# Distribution_amp_10Mhz.net
KiCad netlist of a schematic drawn in Altium Designer
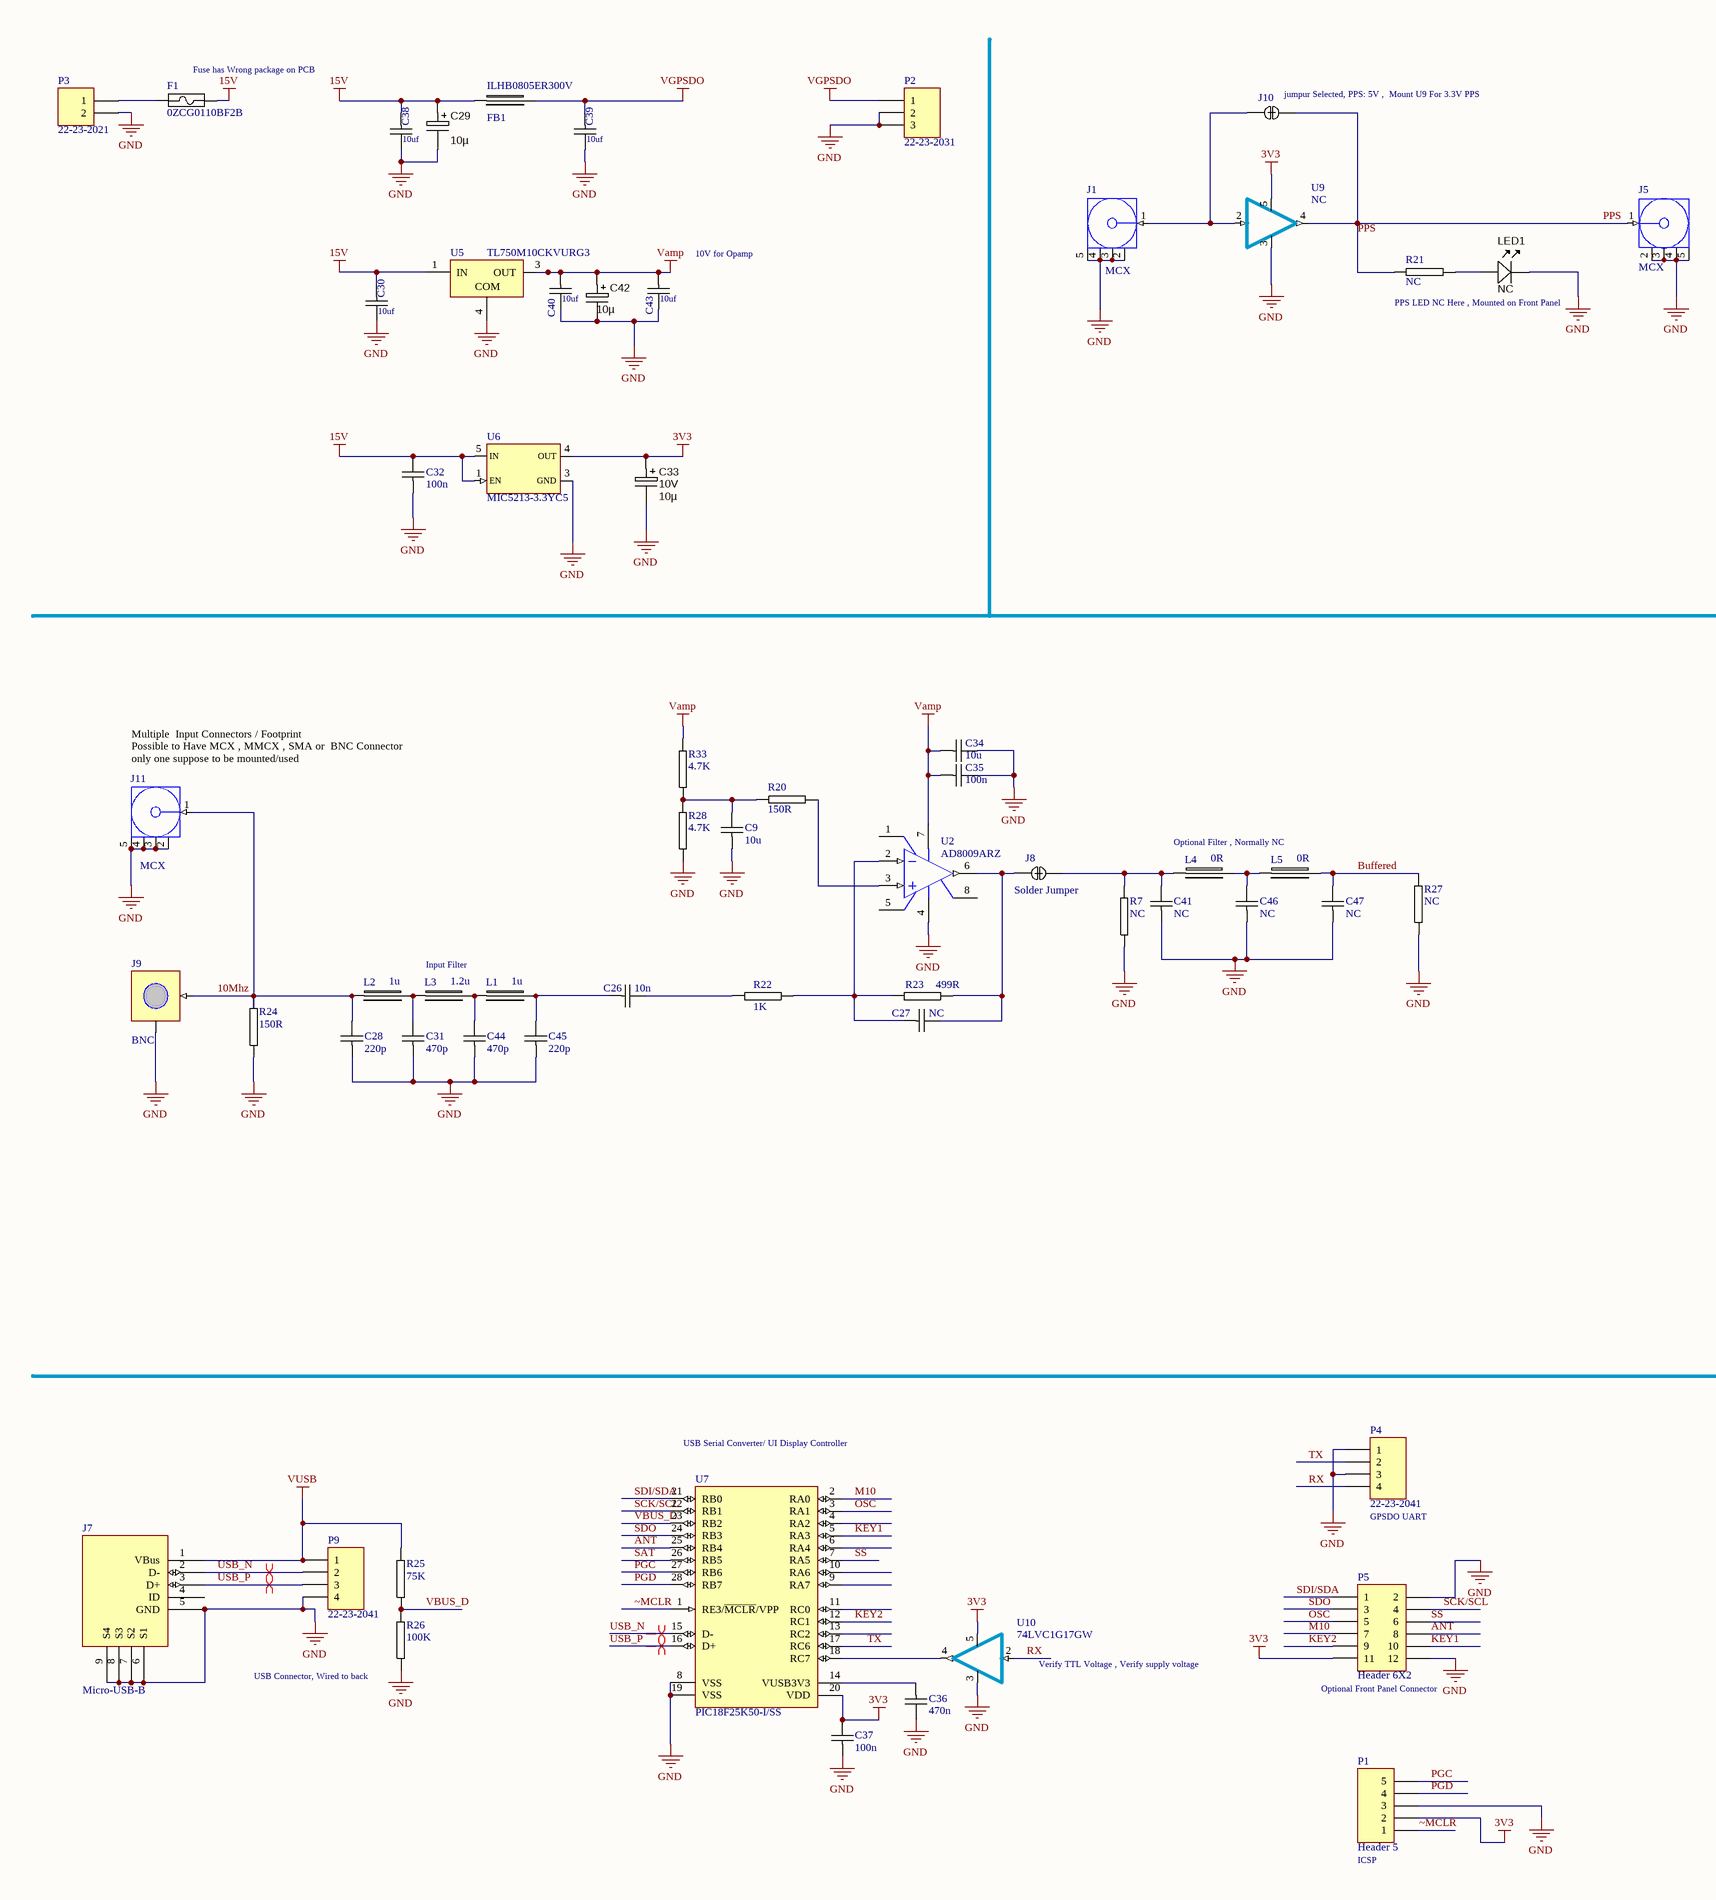
[diagram p0: Distribution_amp_10Mhz.SchDoc, left]
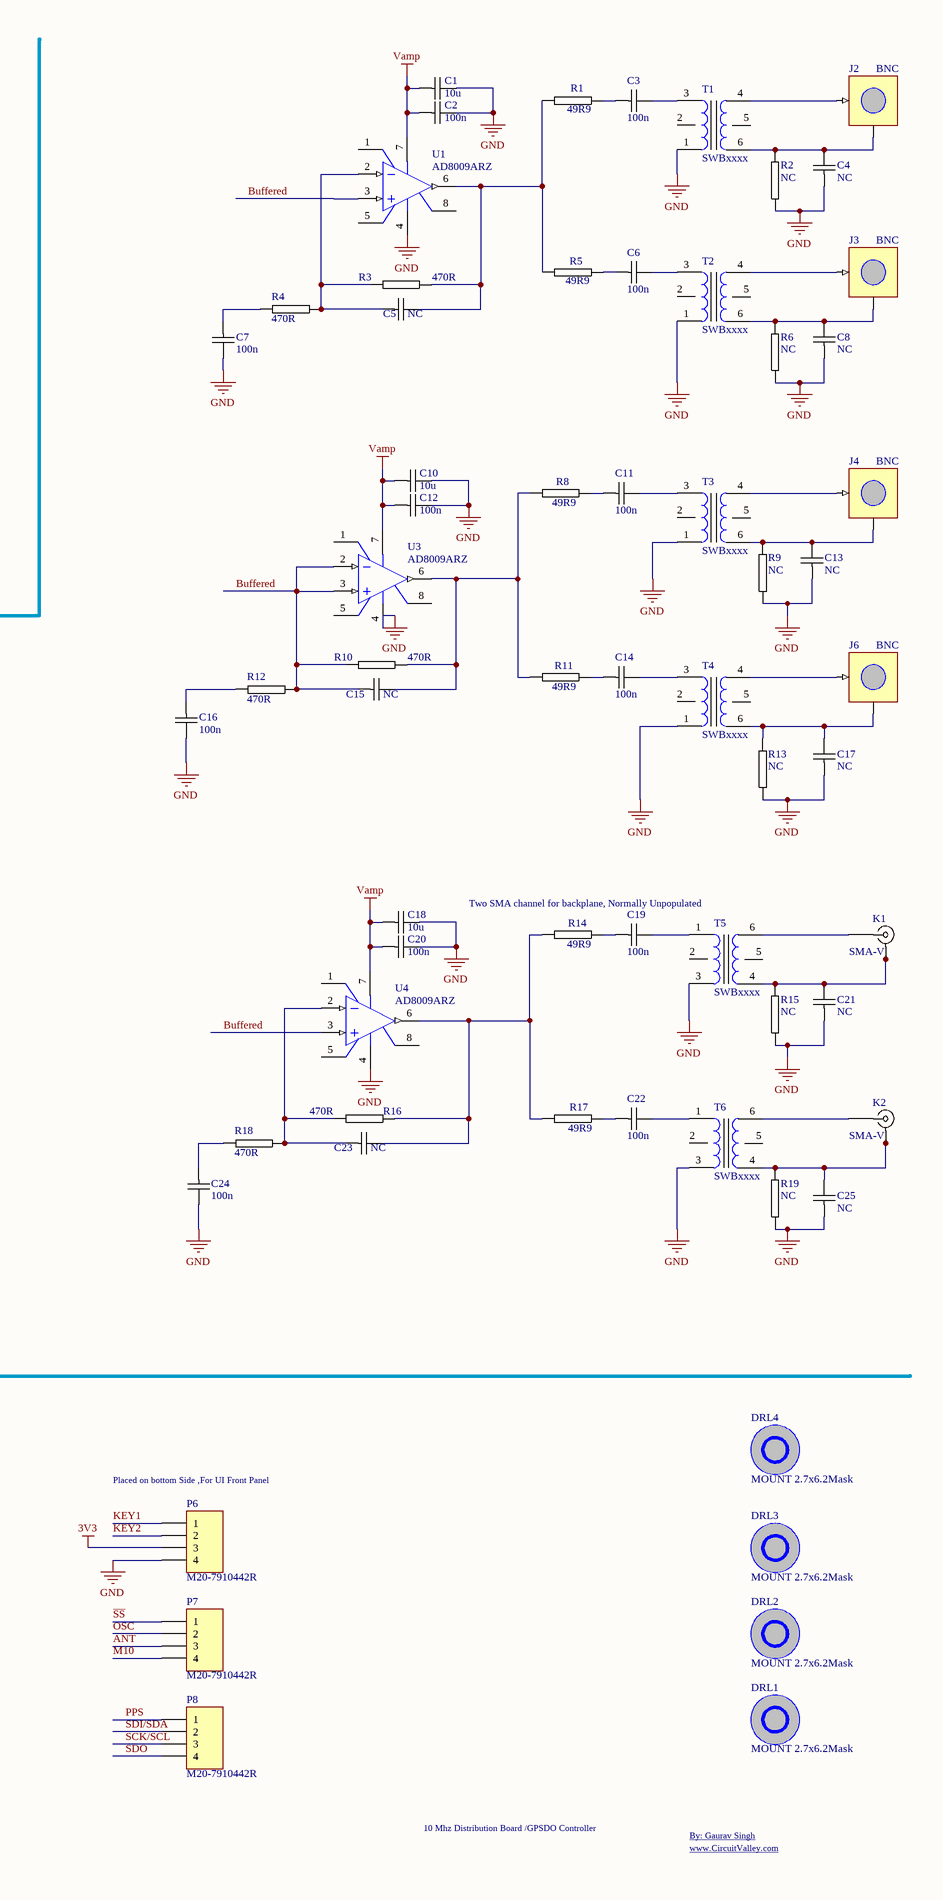
[diagram p1: Distribution_amp_10Mhz.SchDoc, right]

(export (version "E")
  (design (tool "Eeschema 10.0.6"))
  (components
    (comp (ref "C1")
      (value "10u")
      (footprint "0805C-TBD")
      (description "Cap Ceramic 0805")
      (fields (field (name "PART") "GRM21BC81C106KE15L"))
      (libsource (lib "Generic") (part "0805C-TBD"))
    )
    (comp (ref "C2")
      (value "100n")
      (footprint "0805C-TBD")
      (description "Cap Ceramic 0805")
      (fields (field (name "PART") "GRM21BR71H104KA01K"))
      (libsource (lib "Generic") (part "0805C-TBD"))
    )
    (comp (ref "C3")
      (value "100n")
      (footprint "0805C-TBD")
      (description "Cap Ceramic 0805")
      (fields (field (name "PART") "GRM21BR71H104KA01K"))
      (libsource (lib "Generic") (part "0805C-100nF-25V-X7R-MUR"))
    )
    (comp (ref "C4")
      (value "NC")
      (footprint "0805C-TBD")
      (description "Cap Ceramic 0805")
      (libsource (lib "Generic") (part "0805C-100nF-25V-X7R-MUR"))
    )
    (comp (ref "C5")
      (value "NC")
      (footprint "0805C-TBD")
      (description "Cap Ceramic 0805")
      (libsource (lib "Generic") (part "0805C-100nF-25V-X7R-MUR"))
    )
    (comp (ref "C6")
      (value "100n")
      (footprint "0805C-TBD")
      (description "Cap Ceramic 0805")
      (fields (field (name "PART") "GRM21BR71H104KA01K"))
      (libsource (lib "Generic") (part "0805C-100nF-25V-X7R-MUR"))
    )
    (comp (ref "C7")
      (value "100n")
      (footprint "0805C-TBD")
      (description "Cap Ceramic 0805")
      (fields (field (name "PART") "GRM21BR71H104KA01K"))
      (libsource (lib "Generic") (part "0805C-100nF-25V-X7R-MUR"))
    )
    (comp (ref "C8")
      (value "NC")
      (footprint "0805C-TBD")
      (description "Cap Ceramic 0805")
      (libsource (lib "Generic") (part "0805C-100nF-25V-X7R-MUR"))
    )
    (comp (ref "C9")
      (value "10u")
      (footprint "0805C-TBD")
      (description "Cap Ceramic 0805")
      (fields (field (name "PART") "GRM21BC81C106KE15L"))
      (libsource (lib "Generic") (part "0805C-100nF-25V-X7R-MUR"))
    )
    (comp (ref "C10")
      (value "10u")
      (footprint "0805C-TBD")
      (description "Cap Ceramic 0805")
      (fields (field (name "PART") "GRM21BC81C106KE15L"))
      (libsource (lib "Generic") (part "0805C-TBD"))
    )
    (comp (ref "C11")
      (value "100n")
      (footprint "0805C-TBD")
      (description "Cap Ceramic 0805")
      (fields (field (name "PART") "GRM21BR71H104KA01K"))
      (libsource (lib "Generic") (part "0805C-100nF-25V-X7R-MUR"))
    )
    (comp (ref "C12")
      (value "100n")
      (footprint "0805C-TBD")
      (description "Cap Ceramic 0805")
      (fields (field (name "PART") "GRM21BR71H104KA01K"))
      (libsource (lib "Generic") (part "0805C-TBD"))
    )
    (comp (ref "C13")
      (value "NC")
      (footprint "0805C-TBD")
      (description "Cap Ceramic 0805")
      (libsource (lib "Generic") (part "0805C-100nF-25V-X7R-MUR"))
    )
    (comp (ref "C14")
      (value "100n")
      (footprint "0805C-TBD")
      (description "Cap Ceramic 0805")
      (fields (field (name "PART") "GRM21BR71H104KA01K"))
      (libsource (lib "Generic") (part "0805C-100nF-25V-X7R-MUR"))
    )
    (comp (ref "C15")
      (value "NC")
      (footprint "0805C-TBD")
      (description "Cap Ceramic 0805")
      (libsource (lib "Generic") (part "0805C-100nF-25V-X7R-MUR"))
    )
    (comp (ref "C16")
      (value "100n")
      (footprint "0805C-TBD")
      (description "Cap Ceramic 0805")
      (fields (field (name "PART") "GRM21BR71H104KA01K"))
      (libsource (lib "Generic") (part "0805C-100nF-25V-X7R-MUR"))
    )
    (comp (ref "C17")
      (value "NC")
      (footprint "0805C-TBD")
      (description "Cap Ceramic 0805")
      (libsource (lib "Generic") (part "0805C-100nF-25V-X7R-MUR"))
    )
    (comp (ref "C18")
      (value "10u")
      (footprint "0805C-TBD")
      (description "Cap Ceramic 0805")
      (fields (field (name "PART") "GRM21BC81C106KE15L"))
      (libsource (lib "Generic") (part "0805C-TBD"))
    )
    (comp (ref "C19")
      (value "100n")
      (footprint "0805C-TBD")
      (description "Cap Ceramic 0805")
      (fields (field (name "PART") "GRM21BR71H104KA01K"))
      (libsource (lib "Generic") (part "0805C-100nF-25V-X7R-MUR"))
    )
    (comp (ref "C20")
      (value "100n")
      (footprint "0805C-TBD")
      (description "Cap Ceramic 0805")
      (fields (field (name "PART") "GRM21BR71H104KA01K"))
      (libsource (lib "Generic") (part "0805C-TBD"))
    )
    (comp (ref "C21")
      (value "NC")
      (footprint "0805C-TBD")
      (description "Cap Ceramic 0805")
      (libsource (lib "Generic") (part "0805C-100nF-25V-X7R-MUR"))
    )
    (comp (ref "C22")
      (value "100n")
      (footprint "0805C-TBD")
      (description "Cap Ceramic 0805")
      (fields (field (name "PART") "GRM21BR71H104KA01K"))
      (libsource (lib "Generic") (part "0805C-100nF-25V-X7R-MUR"))
    )
    (comp (ref "C23")
      (value "NC")
      (footprint "0805C-TBD")
      (description "Cap Ceramic 0805")
      (libsource (lib "Generic") (part "0805C-100nF-25V-X7R-MUR"))
    )
    (comp (ref "C24")
      (value "100n")
      (footprint "0805C-TBD")
      (description "Cap Ceramic 0805")
      (fields (field (name "PART") "GRM21BR71H104KA01K"))
      (libsource (lib "Generic") (part "0805C-100nF-25V-X7R-MUR"))
    )
    (comp (ref "C25")
      (value "NC")
      (footprint "0805C-TBD")
      (description "Cap Ceramic 0805")
      (libsource (lib "Generic") (part "0805C-100nF-25V-X7R-MUR"))
    )
    (comp (ref "C26")
      (value "10n")
      (footprint "0805C-TBD")
      (description "Cap Ceramic 0805")
      (libsource (lib "Generic") (part "0805C-100nF-25V-X7R-MUR"))
    )
    (comp (ref "C27")
      (value "NC")
      (footprint "0805C-TBD")
      (description "Cap Ceramic 0805")
      (libsource (lib "Generic") (part "0805C-100nF-25V-X7R-MUR"))
    )
    (comp (ref "C28")
      (value "220p")
      (footprint "0805C-TBD")
      (description "Cap Ceramic 0805")
      (fields (field (name "PART") "CC0805FRNPO9BN221"))
      (libsource (lib "Generic") (part "0805C-100nF-25V-X7R-MUR"))
    )
    (comp (ref "C29")
      (value "10µ")
      (footprint "CAPMP3528X210N")
      (description "Capacitor SMD Tantalum 47uF 20% 6.3V 1210")
      (fields (field (name "TOLERANCE") "±20%"))
      (libsource (lib "PBL - Capacitors") (part "CAPT_47u_1210_6V3"))
    )
    (comp (ref "C30")
      (value "10uf")
      (footprint "1210C-GENERIC")
      (description "Cap Ceramic 1210")
      (fields
        (field (name "MANUFACTURER") "Panasonic - ECG")
        (field (name "MANUFACTURER PART NUMBER") "ECJ-4YB0J226M")
      )
      (libsource (lib "Generic") (part "1210C-2u2-35V"))
    )
    (comp (ref "C31")
      (value "470p")
      (footprint "0805C-TBD")
      (description "Cap Ceramic 0805")
      (fields (field (name "PART") "VJ0805Y471JXAPW1BC"))
      (libsource (lib "Generic") (part "0805C-100nF-25V-X7R-MUR"))
    )
    (comp (ref "C32")
      (value "100n")
      (footprint "0603C-GENERIC")
      (description "Cap Ceramic 0603")
      (fields (field (name "PART") "C0603X104K5RAC"))
      (libsource (lib "Generic") (part "0603C-100NF-25V-X7R-TDK"))
    )
    (comp (ref "C33")
      (value "10µ")
      (footprint "CAPMP3528X210N")
      (description "Capacitor SMD Tantalum 47uF 20% 6.3V 1210")
      (fields (field (name "TOLERANCE") "±20%") (field (name "RATINGS") "10V"))
      (libsource (lib "PBL - Capacitors") (part "CAPT_47u_1210_6V3"))
    )
    (comp (ref "C34")
      (value "10u")
      (footprint "0805C-TBD")
      (description "Cap Ceramic 0805")
      (fields (field (name "PART") "GRM21BC81C106KE15L"))
      (libsource (lib "Generic") (part "0805C-TBD"))
    )
    (comp (ref "C35")
      (value "100n")
      (footprint "0805C-TBD")
      (description "Cap Ceramic 0805")
      (libsource (lib "Generic") (part "0805C-TBD"))
    )
    (comp (ref "C36")
      (value "470n")
      (footprint "0805C-TBD")
      (description "Cap Ceramic 0805")
      (fields (field (name "PART") "CL21B474KBFNFNE"))
      (libsource (lib "Generic") (part "0805C-100nF-25V-X7R-MUR"))
    )
    (comp (ref "C37")
      (value "100n")
      (footprint "0805C-TBD")
      (description "Cap Ceramic 0805")
      (fields (field (name "PART") "GRM21BR71H104KA01K"))
      (libsource (lib "Generic") (part "0805C-TBD"))
    )
    (comp (ref "C38")
      (value "10uf")
      (footprint "1210C-GENERIC")
      (description "Cap Ceramic 1210")
      (fields
        (field (name "MANUFACTURER") "Panasonic - ECG")
        (field (name "MANUFACTURER PART NUMBER") "ECJ-4YB0J226M")
      )
      (libsource (lib "Generic") (part "1210C-2u2-35V"))
    )
    (comp (ref "C39")
      (value "10uf")
      (footprint "1210C-GENERIC")
      (description "Cap Ceramic 1210")
      (fields
        (field (name "MANUFACTURER") "Panasonic - ECG")
        (field (name "MANUFACTURER PART NUMBER") "ECJ-4YB0J226M")
      )
      (libsource (lib "Generic") (part "1210C-2u2-35V"))
    )
    (comp (ref "C40")
      (value "10uf")
      (footprint "1210C-GENERIC")
      (description "Cap Ceramic 1210")
      (fields
        (field (name "MANUFACTURER") "Panasonic - ECG")
        (field (name "MANUFACTURER PART NUMBER") "ECJ-4YB0J226M")
      )
      (libsource (lib "Generic") (part "1210C-2u2-35V"))
    )
    (comp (ref "C41")
      (value "NC")
      (footprint "0805C-TBD")
      (description "Cap Ceramic 0805")
      (libsource (lib "Generic") (part "0805C-100nF-25V-X7R-MUR"))
    )
    (comp (ref "C42")
      (value "10µ")
      (footprint "CAPMP3528X210N")
      (description "Capacitor SMD Tantalum 47uF 20% 6.3V 1210")
      (fields (field (name "TOLERANCE") "±20%"))
      (libsource (lib "PBL - Capacitors") (part "CAPT_47u_1210_6V3"))
    )
    (comp (ref "C43")
      (value "10uf")
      (footprint "1210C-GENERIC")
      (description "Cap Ceramic 1210")
      (fields
        (field (name "MANUFACTURER") "Panasonic - ECG")
        (field (name "MANUFACTURER PART NUMBER") "ECJ-4YB0J226M")
      )
      (libsource (lib "Generic") (part "1210C-2u2-35V"))
    )
    (comp (ref "C44")
      (value "470p")
      (footprint "0805C-TBD")
      (description "Cap Ceramic 0805")
      (fields (field (name "PART") "VJ0805Y471JXAPW1BC"))
      (libsource (lib "Generic") (part "0805C-100nF-25V-X7R-MUR"))
    )
    (comp (ref "C45")
      (value "220p")
      (footprint "0805C-TBD")
      (description "Cap Ceramic 0805")
      (fields (field (name "PART") "CC0805FRNPO9BN221"))
      (libsource (lib "Generic") (part "0805C-100nF-25V-X7R-MUR"))
    )
    (comp (ref "C46")
      (value "NC")
      (footprint "0805C-TBD")
      (description "Cap Ceramic 0805")
      (libsource (lib "Generic") (part "0805C-100nF-25V-X7R-MUR"))
    )
    (comp (ref "C47")
      (value "NC")
      (footprint "0805C-TBD")
      (description "Cap Ceramic 0805")
      (libsource (lib "Generic") (part "0805C-100nF-25V-X7R-MUR"))
    )
    (comp (ref "DRL1")
      (value "MOUNT 2.7x6.2Mask")
      (footprint "NO_COPPER_NOMASK_2m75_6m2")
      (libsource (lib "mounting_hole") (part "DRILL_2.7x6.2Mask_NOCOPPER"))
    )
    (comp (ref "DRL2")
      (value "MOUNT 2.7x6.2Mask")
      (footprint "NO_COPPER_NOMASK_2m75_6m2")
      (libsource (lib "mounting_hole") (part "DRILL_2.7x6.2Mask_NOCOPPER"))
    )
    (comp (ref "DRL3")
      (value "MOUNT 2.7x6.2Mask")
      (footprint "NO_COPPER_NOMASK_2m75_6m2")
      (libsource (lib "mounting_hole") (part "DRILL_2.7x6.2Mask_NOCOPPER"))
    )
    (comp (ref "DRL4")
      (value "MOUNT 2.7x6.2Mask")
      (footprint "NO_COPPER_NOMASK_2m75_6m2")
      (libsource (lib "mounting_hole") (part "DRILL_2.7x6.2Mask_NOCOPPER"))
    )
    (comp (ref "F1")
      (value "0ZCG0110BF2B")
      (footprint "RESC3216N")
      (description "GENERIC FUSE")
      (libsource (lib "Generic") (part "FUSE-GENERIC"))
    )
    (comp (ref "FB1")
      (value "ILHB0805ER300V")
      (footprint "0805FB-600Z")
      (description "FERRITE BEAD 600 OHM 2A")
      (libsource (lib "Generic") (part "0805FB-600Z"))
    )
    (comp (ref "J1")
      (value "MCX")
      (footprint "CON-MCX")
      (description "MCX Female PCB Mount Connector, Thru-Hole")
      (fields (field (name "PART") "919-382J-51P"))
      (libsource (lib "Linx Technologies Connector") (part "CONMCX001"))
    )
    (comp (ref "J2")
      (value "BNC")
      (footprint "BNC 1-1634612-0")
      (fields (field (name "PART") "1-1337543-0 / 1-1634612-0"))
      (libsource (lib "cvlib") (part "BNC Connector"))
    )
    (comp (ref "J3")
      (value "BNC")
      (footprint "BNC 1-1634612-0")
      (fields (field (name "PART") "1-1337543-0 / 1-1634612-0"))
      (libsource (lib "cvlib") (part "BNC Connector"))
    )
    (comp (ref "J4")
      (value "BNC")
      (footprint "BNC 1-1634612-0")
      (fields (field (name "PART") "1-1337543-0 / 1-1634612-0"))
      (libsource (lib "cvlib") (part "BNC Connector"))
    )
    (comp (ref "J5")
      (value "MCX")
      (footprint "CON-REVMCX")
      (description "RP-MCX Female PCB Mount Connector")
      (fields (field (name "PART") "919-382J-51P"))
      (libsource (lib "Linx Technologies Connector") (part "CONREVMCX001"))
    )
    (comp (ref "J6")
      (value "BNC")
      (footprint "BNC 1-1634612-0")
      (fields (field (name "PART") "1-1337543-0 / 1-1634612-0"))
      (libsource (lib "cvlib") (part "BNC Connector"))
    )
    (comp (ref "J7")
      (value "Micro-USB-B")
      (footprint "10118193-0001lfc")
      (fields (field (name "PART") "10118193-0001lfc"))
      (libsource (lib "USB-MICROB-HW-MC-5F") (part "Micro-USB-B"))
    )
    (comp (ref "J8")
      (value "Solder Jumper")
      (footprint "BYPASS-MINI-CLOSED")
      (libsource (lib "Generic") (part "BYPASS-MINI-CLOSED"))
    )
    (comp (ref "J9")
      (value "BNC")
      (footprint "BNC 1-1634612-0")
      (fields (field (name "PART") "1-1337543-0 / 1-1634612-0"))
      (libsource (lib "") (part "BNC Connector_1"))
    )
    (comp (ref "J10")
      (value "Solder Jumper")
      (footprint "BYPASS-CLOSED")
      (libsource (lib "Generic") (part "BYPASS-CLOSED"))
    )
    (comp (ref "J11")
      (value "MCX")
      (footprint "CON-REVMCX")
      (description "RP-MCX Female PCB Mount Connector")
      (fields (field (name "PART") "919-382J-51P"))
      (libsource (lib "Linx Technologies Connector") (part "CONREVMCX001"))
    )
    (comp (ref "K1")
      (value "SMA-V")
      (footprint "SMA-V")
      (description "SMA THREADED RF CONNECTOR VERTICAL")
      (fields (field (name "PART") "NC"))
      (libsource (lib "Generic") (part "SMA-V"))
    )
    (comp (ref "K2")
      (value "SMA-V")
      (footprint "SMA-V")
      (description "SMA THREADED RF CONNECTOR VERTICAL")
      (fields (field (name "PART") "NC"))
      (libsource (lib "Generic") (part "SMA-V"))
    )
    (comp (ref "L1")
      (value "1u")
      (footprint "0805FB-GENERIC")
      (description "Inductor")
      (fields (field (name "PART") "0805LS-102XGEB"))
      (libsource (lib "Generic") (part "0805FB-GENERIC"))
    )
    (comp (ref "L2")
      (value "1u")
      (footprint "0805FB-GENERIC")
      (description "Inductor")
      (fields (field (name "PART") "0805LS-102XGEB"))
      (libsource (lib "Generic") (part "0805FB-GENERIC"))
    )
    (comp (ref "L3")
      (value "1.2u")
      (footprint "0805FB-GENERIC")
      (description "Inductor")
      (fields (field (name "PART") "0805LS-122XGEB"))
      (libsource (lib "Generic") (part "0805FB-GENERIC"))
    )
    (comp (ref "L4")
      (value "0R")
      (footprint "0805FB-GENERIC")
      (description "Inductor")
      (fields (field (name "PART") "RC0805FR-070RL"))
      (libsource (lib "Generic") (part "0805FB-GENERIC"))
    )
    (comp (ref "L5")
      (value "0R")
      (footprint "0805FB-GENERIC")
      (description "Inductor")
      (fields (field (name "PART") "RC0805FR-070RL"))
      (libsource (lib "Generic") (part "0805FB-GENERIC"))
    )
    (comp (ref "LED1")
      (value "NC")
      (footprint "LED-0805-K")
      (description "LED, 0805 SMD, Green")
      (libsource (lib "PBL - Light Sources") (part "LED_SMD_Green_0805"))
    )
    (comp (ref "P1")
      (value "Header 5")
      (footprint "HDR1X5")
      (description "Header, 5-Pin")
      (fields (field (name "PUBLISHER") "Altium Limited"))
      (libsource (lib "Miscellaneous Connectors") (part "Header 5"))
    )
    (comp (ref "P2")
      (value "22-23-2031")
      (footprint "22-23-2031")
      (description "Header, 3-Pin")
      (fields (field (name "PUBLISHER") "Altium Limited"))
      (libsource (lib "Miscellaneous Connectors") (part "Header 3"))
    )
    (comp (ref "P3")
      (value "22-23-2021")
      (footprint "22-23-2021")
      (description "Header, 2-Pin")
      (fields (field (name "PUBLISHER") "Altium Limited"))
      (libsource (lib "Miscellaneous Connectors") (part "Header 2"))
    )
    (comp (ref "P4")
      (value "22-23-2041")
      (footprint "22-23-2041")
      (description "Header, 4-Pin")
      (fields (field (name "PUBLISHER") "Altium Limited"))
      (libsource (lib "Miscellaneous Connectors") (part "Header 4"))
    )
    (comp (ref "P5")
      (value "Header 6X2")
      (footprint "HDR2X6")
      (description "Header, 6-Pin, Dual row")
      (fields (field (name "PUBLISHER") "Altium Limited"))
      (libsource (lib "Miscellaneous Connectors") (part "Header 6X2"))
    )
    (comp (ref "P6")
      (value "M20-7910442R")
      (footprint "M20-7910442R")
      (description "SMD Female Header")
      (libsource (lib "Miscellaneous Connectors") (part "Header 4"))
    )
    (comp (ref "P7")
      (value "M20-7910442R")
      (footprint "M20-7910442R")
      (description "SMD Female Header")
      (libsource (lib "Miscellaneous Connectors") (part "Header 4"))
    )
    (comp (ref "P8")
      (value "M20-7910442R")
      (footprint "M20-7910442R")
      (description "SMD Female Header")
      (libsource (lib "Miscellaneous Connectors") (part "Header 4"))
    )
    (comp (ref "P9")
      (value "22-23-2041")
      (footprint "22-23-2041")
      (description "Header, 4-Pin")
      (fields (field (name "PUBLISHER") "Altium Limited"))
      (libsource (lib "Miscellaneous Connectors") (part "Header 4"))
    )
    (comp (ref "R1")
      (value "49R9")
      (footprint "0805R-GENERIC")
      (description "Resistor 0805")
      (fields (field (name "PART") "NRC10F49R9TRF"))
      (libsource (lib "Generic") (part "0805R-0R"))
    )
    (comp (ref "R2")
      (value "NC")
      (footprint "0805R-GENERIC")
      (description "Resistor 0805")
      (libsource (lib "Generic") (part "0805R-0R"))
    )
    (comp (ref "R3")
      (value "470R")
      (footprint "0805R-GENERIC")
      (description "Resistor 0805")
      (fields (field (name "PART") "RR1220P-471-D"))
      (libsource (lib "Generic") (part "0805R-0R"))
    )
    (comp (ref "R4")
      (value "470R")
      (footprint "0805R-GENERIC")
      (description "Resistor 0805")
      (fields (field (name "PART") "RR1220P-471-D"))
      (libsource (lib "Generic") (part "0805R-0R"))
    )
    (comp (ref "R5")
      (value "49R9")
      (footprint "0805R-GENERIC")
      (description "Resistor 0805")
      (fields (field (name "PART") "NRC10F49R9TRF"))
      (libsource (lib "Generic") (part "0805R-0R"))
    )
    (comp (ref "R6")
      (value "NC")
      (footprint "0805R-GENERIC")
      (description "Resistor 0805")
      (libsource (lib "Generic") (part "0805R-0R"))
    )
    (comp (ref "R7")
      (value "NC")
      (footprint "0805R-GENERIC")
      (description "Resistor 0805")
      (libsource (lib "Generic") (part "0805R-0R"))
    )
    (comp (ref "R8")
      (value "49R9")
      (footprint "0805R-GENERIC")
      (description "Resistor 0805")
      (fields (field (name "PART") "NRC10F49R9TRF"))
      (libsource (lib "Generic") (part "0805R-0R"))
    )
    (comp (ref "R9")
      (value "NC")
      (footprint "0805R-GENERIC")
      (description "Resistor 0805")
      (libsource (lib "Generic") (part "0805R-0R"))
    )
    (comp (ref "R10")
      (value "470R")
      (footprint "0805R-GENERIC")
      (description "Resistor 0805")
      (fields (field (name "PART") "RR1220P-471-D"))
      (libsource (lib "Generic") (part "0805R-0R"))
    )
    (comp (ref "R11")
      (value "49R9")
      (footprint "0805R-GENERIC")
      (description "Resistor 0805")
      (fields (field (name "PART") "NRC10F49R9TRF"))
      (libsource (lib "Generic") (part "0805R-0R"))
    )
    (comp (ref "R12")
      (value "470R")
      (footprint "0805R-GENERIC")
      (description "Resistor 0805")
      (fields (field (name "PART") "RR1220P-471-D"))
      (libsource (lib "Generic") (part "0805R-0R"))
    )
    (comp (ref "R13")
      (value "NC")
      (footprint "0805R-GENERIC")
      (description "Resistor 0805")
      (libsource (lib "Generic") (part "0805R-0R"))
    )
    (comp (ref "R14")
      (value "49R9")
      (footprint "0805R-GENERIC")
      (description "Resistor 0805")
      (fields (field (name "PART") "NRC10F49R9TRF"))
      (libsource (lib "Generic") (part "0805R-0R"))
    )
    (comp (ref "R15")
      (value "NC")
      (footprint "0805R-GENERIC")
      (description "Resistor 0805")
      (libsource (lib "Generic") (part "0805R-0R"))
    )
    (comp (ref "R16")
      (value "470R")
      (footprint "0805R-GENERIC")
      (description "Resistor 0805")
      (fields (field (name "PART") "RR1220P-471-D"))
      (libsource (lib "Generic") (part "0805R-0R"))
    )
    (comp (ref "R17")
      (value "49R9")
      (footprint "0805R-GENERIC")
      (description "Resistor 0805")
      (fields (field (name "PART") "NRC10F49R9TRF"))
      (libsource (lib "Generic") (part "0805R-0R"))
    )
    (comp (ref "R18")
      (value "470R")
      (footprint "0805R-GENERIC")
      (description "Resistor 0805")
      (fields (field (name "PART") "RR1220P-471-D"))
      (libsource (lib "Generic") (part "0805R-0R"))
    )
    (comp (ref "R19")
      (value "NC")
      (footprint "0805R-GENERIC")
      (description "Resistor 0805")
      (libsource (lib "Generic") (part "0805R-0R"))
    )
    (comp (ref "R20")
      (value "150R")
      (footprint "0805R-GENERIC")
      (description "Resistor 0805")
      (fields (field (name "PART") "RK73H2ATTDD1500F"))
      (libsource (lib "Generic") (part "0805R-0R"))
    )
    (comp (ref "R21")
      (value "NC")
      (footprint "0805R-GENERIC")
      (description "Resistor 0805")
      (libsource (lib "Generic") (part "0805R-0R"))
    )
    (comp (ref "R22")
      (value "1K")
      (footprint "0805R-GENERIC")
      (description "Resistor 0805")
      (fields (field (name "PART") "RC0805FR-131KL"))
      (libsource (lib "Generic") (part "0805R-0R"))
    )
    (comp (ref "R23")
      (value "499R")
      (footprint "0805R-GENERIC")
      (description "Resistor 0805")
      (fields (field (name "PART") "RC0805FR-07499RL"))
      (libsource (lib "Generic") (part "0805R-0R"))
    )
    (comp (ref "R24")
      (value "150R")
      (footprint "0805R-GENERIC")
      (description "Resistor 0805")
      (fields (field (name "PART") "RK73H2ATTDD1500F"))
      (libsource (lib "Generic") (part "0805R-0R"))
    )
    (comp (ref "R25")
      (value "75K")
      (footprint "0805R-GENERIC")
      (description "Resistor 0805")
      (fields (field (name "PART") "RR1220P-753-D"))
      (libsource (lib "Generic") (part "0805R-0R"))
    )
    (comp (ref "R26")
      (value "100K")
      (footprint "0805R-GENERIC")
      (description "Resistor 0805")
      (fields (field (name "PART") "CRCW0805100KFKEA"))
      (libsource (lib "Generic") (part "0805R-0R"))
    )
    (comp (ref "R27")
      (value "NC")
      (footprint "0805R-GENERIC")
      (description "Resistor 0805")
      (libsource (lib "Generic") (part "0805R-0R"))
    )
    (comp (ref "R28")
      (value "4.7K")
      (footprint "0805R-GENERIC")
      (description "Resistor 0805")
      (fields (field (name "PART") "ERA6AEB472V"))
      (libsource (lib "Generic") (part "0805R-0R"))
    )
    (comp (ref "R33")
      (value "4.7K")
      (footprint "0805R-GENERIC")
      (description "Resistor 0805")
      (fields (field (name "PART") "ERA6AEB472V"))
      (libsource (lib "Generic") (part "0805R-0R"))
    )
    (comp (ref "T1")
      (value "SWBxxxx")
      (footprint "SWBxxxx")
      (description "RF Transformer")
      (fields (field (name "PART") "SWB1010"))
      (libsource (lib "") (part "Transformer SWBxxxx_1"))
    )
    (comp (ref "T2")
      (value "SWBxxxx")
      (footprint "SWBxxxx")
      (description "RF Transformer")
      (fields (field (name "PART") "SWB1010"))
      (libsource (lib "") (part "Transformer SWBxxxx_1"))
    )
    (comp (ref "T3")
      (value "SWBxxxx")
      (footprint "SWBxxxx")
      (description "RF Transformer")
      (fields (field (name "PART") "SWB1010"))
      (libsource (lib "") (part "Transformer SWBxxxx_1"))
    )
    (comp (ref "T4")
      (value "SWBxxxx")
      (footprint "SWBxxxx")
      (description "RF Transformer")
      (fields (field (name "PART") "SWB1010"))
      (libsource (lib "") (part "Transformer SWBxxxx_1"))
    )
    (comp (ref "T5")
      (value "SWBxxxx")
      (footprint "SWBxxxx")
      (description "RF Transformer")
      (fields (field (name "PART") "SWB1010"))
      (libsource (lib "cvlib") (part "Transformer SWBxxxx"))
    )
    (comp (ref "T6")
      (value "SWBxxxx")
      (footprint "SWBxxxx")
      (description "RF Transformer")
      (fields (field (name "PART") "SWB1010"))
      (libsource (lib "cvlib") (part "Transformer SWBxxxx"))
    )
    (comp (ref "U1")
      (value "AD8009ARZ")
      (footprint "M08A_N")
      (description "Very High Speed, High Output Current, Voltage Feedback Amplifier, 8-pin Narrow SOIC")
      (libsource (lib "NSC Amplifier") (part "LM7171AIM"))
    )
    (comp (ref "U2")
      (value "AD8009ARZ")
      (footprint "M08A_N")
      (description "Very High Speed, High Output Current, Voltage Feedback Amplifier, 8-pin Narrow SOIC")
      (libsource (lib "NSC Amplifier") (part "LM7171AIM"))
    )
    (comp (ref "U3")
      (value "AD8009ARZ")
      (footprint "M08A_N")
      (description "Very High Speed, High Output Current, Voltage Feedback Amplifier, 8-pin Narrow SOIC")
      (libsource (lib "NSC Amplifier") (part "LM7171AIM"))
    )
    (comp (ref "U4")
      (value "AD8009ARZ")
      (footprint "M08A_N")
      (description "Very High Speed, High Output Current, Voltage Feedback Amplifier, 8-pin Narrow SOIC")
      (libsource (lib "NSC Amplifier") (part "LM7171AIM"))
    )
    (comp (ref "U5")
      (value "TL750M10CKVURG3")
      (footprint "TI-KVU3_N")
      (description "Single Output LDO, 750 mA, Fixed 10 V Output, 11 to 26 V")
      (fields (field (name "MANUFACTURER") "Texas Instruments"))
      (libsource (lib "TI Power Management Linear Regulator Single Channel LDO (400-7500mA)") (part "TL750M10CKVURG3"))
    )
    (comp (ref "U6")
      (value "MIC5213-3.3YC5")
      (footprint "SC70-5")
      (description "LDO 3.3V")
      (libsource (lib "cvlib") (part "MIC5213"))
    )
    (comp (ref "U7")
      (value "PIC18F25K50-I/SS")
      (footprint "MCHP-SSOP-SS28_N")
      (fields (field (name "MANUFACTURER") "Microchip"))
      (libsource (lib "Microchip PIC18") (part "PIC18F25K50-I/SS"))
    )
    (comp (ref "U9")
      (value "NC")
      (footprint "SC70-5")
      (description "Logic Buffer")
      (fields (field (name "PART") "74LVC1G17GW-Q100"))
      (libsource (lib "cvlib") (part "74LVC1G17GW-Q100"))
    )
    (comp (ref "U10")
      (value "74LVC1G17GW")
      (footprint "SC70-5")
      (description "Logic Buffer")
      (fields (field (name "PART") "74LVC1G17GW-Q100"))
      (libsource (lib "cvlib") (part "74LVC1G17GW-Q100"))
    )
  )
  (nets
    (net (code "1") (name "/10Mhz") (class "Default")
      (node (ref "C28") (pin "2") (pintype "passive"))
      (node (ref "J11") (pin "1") (pinfunction "Signal_1") (pintype "input"))
      (node (ref "J9") (pin "1") (pinfunction "1_1") (pintype "input"))
      (node (ref "L2") (pin "1") (pintype "passive"))
      (node (ref "R24") (pin "2") (pintype "passive"))
    )
    (net (code "2") (name "/ANT") (class "Default")
      (node (ref "P5") (pin "8") (pinfunction "8_8") (pintype "passive"))
      (node (ref "P7") (pin "3") (pinfunction "3_3") (pintype "passive"))
      (node (ref "U7") (pin "25") (pinfunction "RB4_25") (pintype "bidirectional"))
    )
    (net (code "3") (name "/Buffered") (class "Default")
      (node (ref "C15") (pin "1") (pintype "passive"))
      (node (ref "C47") (pin "2") (pintype "passive"))
      (node (ref "L5") (pin "2") (pintype "passive"))
      (node (ref "R10") (pin "1") (pintype "passive"))
      (node (ref "R12") (pin "2") (pintype "passive"))
      (node (ref "R27") (pin "2") (pintype "passive"))
      (node (ref "U1") (pin "3") (pinfunction "IN+_3") (pintype "input"))
      (node (ref "U3") (pin "2") (pinfunction "IN-_2") (pintype "input"))
      (node (ref "U3") (pin "3") (pinfunction "IN+_3") (pintype "input"))
      (node (ref "U4") (pin "3") (pinfunction "IN+_3") (pintype "input"))
    )
    (net (code "4") (name "/KEY1") (class "Default")
      (node (ref "P5") (pin "10") (pinfunction "10_10") (pintype "passive"))
      (node (ref "P6") (pin "1") (pinfunction "1_1") (pintype "passive"))
      (node (ref "U7") (pin "5") (pinfunction "RA3_5") (pintype "bidirectional"))
    )
    (net (code "5") (name "/KEY2") (class "Default")
      (node (ref "P5") (pin "9") (pinfunction "9_9") (pintype "passive"))
      (node (ref "P6") (pin "2") (pinfunction "2_2") (pintype "passive"))
      (node (ref "U7") (pin "12") (pinfunction "RC1_12") (pintype "bidirectional"))
    )
    (net (code "6") (name "/M10") (class "Default")
      (node (ref "P5") (pin "7") (pinfunction "7_7") (pintype "passive"))
      (node (ref "P7") (pin "4") (pinfunction "4_4") (pintype "passive"))
      (node (ref "U7") (pin "2") (pinfunction "RA0_2") (pintype "bidirectional"))
    )
    (net (code "7") (name "/OSC") (class "Default")
      (node (ref "P5") (pin "5") (pinfunction "5_5") (pintype "passive"))
      (node (ref "P7") (pin "2") (pinfunction "2_2") (pintype "passive"))
      (node (ref "U7") (pin "3") (pinfunction "RA1_3") (pintype "bidirectional"))
    )
    (net (code "8") (name "/PGC") (class "Default")
      (node (ref "P1") (pin "5") (pinfunction "5_5") (pintype "passive"))
      (node (ref "U7") (pin "27") (pinfunction "RB6_27") (pintype "bidirectional"))
    )
    (net (code "9") (name "/PGD") (class "Default")
      (node (ref "P1") (pin "4") (pinfunction "4_4") (pintype "passive"))
      (node (ref "U7") (pin "28") (pinfunction "RB7_28") (pintype "bidirectional"))
    )
    (net (code "10") (name "/PPS") (class "Default")
      (node (ref "J10") (pin "1") (pinfunction "1_1") (pintype "passive"))
      (node (ref "J5") (pin "1") (pinfunction "Signal_1") (pintype "input"))
      (node (ref "P8") (pin "1") (pinfunction "1_1") (pintype "passive"))
      (node (ref "R21") (pin "2") (pintype "passive"))
      (node (ref "U9") (pin "4") (pinfunction "3_4") (pintype "output"))
    )
    (net (code "11") (name "/RX") (class "Default")
      (node (ref "P4") (pin "4") (pinfunction "4_4") (pintype "passive"))
      (node (ref "U10") (pin "2") (pinfunction "2_2") (pintype "input"))
    )
    (net (code "12") (name "/SAT") (class "Default")
      (node (ref "U7") (pin "26") (pinfunction "RB5_26") (pintype "bidirectional"))
    )
    (net (code "13") (name "/SCK{slash}SCL") (class "Default")
      (node (ref "P5") (pin "4") (pinfunction "4_4") (pintype "passive"))
      (node (ref "P8") (pin "3") (pinfunction "3_3") (pintype "passive"))
      (node (ref "U7") (pin "22") (pinfunction "RB1_22") (pintype "bidirectional"))
    )
    (net (code "14") (name "/SDI{slash}SDA") (class "Default")
      (node (ref "P5") (pin "1") (pinfunction "1_1") (pintype "passive"))
      (node (ref "P8") (pin "2") (pinfunction "2_2") (pintype "passive"))
      (node (ref "U7") (pin "21") (pinfunction "RB0_21") (pintype "bidirectional"))
    )
    (net (code "15") (name "/SDO") (class "Default")
      (node (ref "P5") (pin "3") (pinfunction "3_3") (pintype "passive"))
      (node (ref "P8") (pin "4") (pinfunction "4_4") (pintype "passive"))
      (node (ref "U7") (pin "24") (pinfunction "RB3_24") (pintype "bidirectional"))
    )
    (net (code "16") (name "/TX") (class "Default")
      (node (ref "P4") (pin "2") (pinfunction "2_2") (pintype "passive"))
      (node (ref "U7") (pin "17") (pinfunction "RC6_17") (pintype "bidirectional"))
    )
    (net (code "17") (name "/USB_N") (class "Default")
      (node (ref "J7") (pin "2") (pinfunction "D-_2") (pintype "bidirectional"))
      (node (ref "P9") (pin "2") (pinfunction "2_2") (pintype "passive"))
      (node (ref "U7") (pin "15") (pinfunction "D-_15") (pintype "bidirectional"))
    )
    (net (code "18") (name "/USB_P") (class "Default")
      (node (ref "J7") (pin "3") (pinfunction "D+_3") (pintype "bidirectional"))
      (node (ref "P9") (pin "3") (pinfunction "3_3") (pintype "passive"))
      (node (ref "U7") (pin "16") (pinfunction "D+_16") (pintype "bidirectional"))
    )
    (net (code "19") (name "/VBUS_D") (class "Default")
      (node (ref "R25") (pin "1") (pintype "passive"))
      (node (ref "R26") (pin "2") (pintype "passive"))
      (node (ref "U7") (pin "23") (pinfunction "RB2_23") (pintype "bidirectional"))
    )
    (net (code "20") (name "/~MCLR") (class "Default")
      (node (ref "P1") (pin "1") (pinfunction "1_1") (pintype "passive"))
      (node (ref "U7") (pin "1") (pinfunction "RE3/~{MCLR}/VPP_1") (pintype "input"))
    )
    (net (code "21") (name "/~{SS}") (class "Default")
      (node (ref "P5") (pin "6") (pinfunction "6_6") (pintype "passive"))
      (node (ref "P7") (pin "1") (pinfunction "1_1") (pintype "passive"))
      (node (ref "U7") (pin "7") (pinfunction "RA5_7") (pintype "bidirectional"))
    )
    (net (code "22") (name "3V3") (class "Default")
      (node (ref "C33") (pin "1") (pintype "passive"))
      (node (ref "C37") (pin "2") (pintype "passive"))
      (node (ref "P1") (pin "2") (pinfunction "2_2") (pintype "passive"))
      (node (ref "P5") (pin "11") (pinfunction "11_11") (pintype "passive"))
      (node (ref "P6") (pin "3") (pinfunction "3_3") (pintype "passive"))
      (node (ref "U10") (pin "5") (pinfunction "VCC_5") (pintype "power_in"))
      (node (ref "U6") (pin "4") (pinfunction "OUT_4") (pintype "power_in"))
      (node (ref "U7") (pin "20") (pinfunction "VDD_20") (pintype "power_in"))
      (node (ref "U9") (pin "5") (pinfunction "VCC_5") (pintype "power_in"))
    )
    (net (code "23") (name "15V") (class "Default")
      (node (ref "C29") (pin "1") (pintype "passive"))
      (node (ref "C30") (pin "1") (pintype "passive"))
      (node (ref "C32") (pin "2") (pintype "passive"))
      (node (ref "C38") (pin "1") (pintype "passive"))
      (node (ref "F1") (pin "1") (pintype "passive"))
      (node (ref "FB1") (pin "1") (pintype "passive"))
      (node (ref "U5") (pin "1") (pinfunction "IN_1") (pintype "power_in"))
      (node (ref "U6") (pin "1") (pinfunction "EN_1") (pintype "input"))
      (node (ref "U6") (pin "5") (pinfunction "IN_5") (pintype "power_in"))
    )
    (net (code "24") (name "GND") (class "Default")
      (node (ref "C1") (pin "2") (pintype "passive"))
      (node (ref "C10") (pin "2") (pintype "passive"))
      (node (ref "C12") (pin "2") (pintype "passive"))
      (node (ref "C13") (pin "1") (pintype "passive"))
      (node (ref "C16") (pin "2") (pintype "passive"))
      (node (ref "C17") (pin "1") (pintype "passive"))
      (node (ref "C18") (pin "2") (pintype "passive"))
      (node (ref "C2") (pin "2") (pintype "passive"))
      (node (ref "C20") (pin "2") (pintype "passive"))
      (node (ref "C21") (pin "1") (pintype "passive"))
      (node (ref "C24") (pin "2") (pintype "passive"))
      (node (ref "C25") (pin "1") (pintype "passive"))
      (node (ref "C28") (pin "1") (pintype "passive"))
      (node (ref "C29") (pin "2") (pintype "passive"))
      (node (ref "C30") (pin "2") (pintype "passive"))
      (node (ref "C31") (pin "1") (pintype "passive"))
      (node (ref "C32") (pin "1") (pintype "passive"))
      (node (ref "C33") (pin "2") (pintype "passive"))
      (node (ref "C34") (pin "2") (pintype "passive"))
      (node (ref "C35") (pin "2") (pintype "passive"))
      (node (ref "C36") (pin "2") (pintype "passive"))
      (node (ref "C37") (pin "1") (pintype "passive"))
      (node (ref "C38") (pin "2") (pintype "passive"))
      (node (ref "C39") (pin "2") (pintype "passive"))
      (node (ref "C4") (pin "1") (pintype "passive"))
      (node (ref "C40") (pin "2") (pintype "passive"))
      (node (ref "C41") (pin "1") (pintype "passive"))
      (node (ref "C42") (pin "2") (pintype "passive"))
      (node (ref "C43") (pin "2") (pintype "passive"))
      (node (ref "C44") (pin "1") (pintype "passive"))
      (node (ref "C45") (pin "1") (pintype "passive"))
      (node (ref "C46") (pin "1") (pintype "passive"))
      (node (ref "C47") (pin "1") (pintype "passive"))
      (node (ref "C7") (pin "2") (pintype "passive"))
      (node (ref "C8") (pin "1") (pintype "passive"))
      (node (ref "C9") (pin "1") (pintype "passive"))
      (node (ref "J1") (pin "2") (pinfunction "GND_2") (pintype "power_in"))
      (node (ref "J1") (pin "3") (pinfunction "GND_3") (pintype "power_in"))
      (node (ref "J1") (pin "4") (pinfunction "GND_4") (pintype "power_in"))
      (node (ref "J1") (pin "5") (pinfunction "GND_5") (pintype "power_in"))
      (node (ref "J11") (pin "2") (pinfunction "GND_2") (pintype "power_in"))
      (node (ref "J11") (pin "3") (pinfunction "GND_3") (pintype "power_in"))
      (node (ref "J11") (pin "4") (pinfunction "GND_4") (pintype "power_in"))
      (node (ref "J11") (pin "5") (pinfunction "GND_5") (pintype "power_in"))
      (node (ref "J5") (pin "2") (pinfunction "GND_2") (pintype "power_in"))
      (node (ref "J5") (pin "3") (pinfunction "GND_3") (pintype "power_in"))
      (node (ref "J5") (pin "4") (pinfunction "GND_4") (pintype "power_in"))
      (node (ref "J5") (pin "5") (pinfunction "GND_5") (pintype "power_in"))
      (node (ref "J7") (pin "5") (pinfunction "GND_5") (pintype "power_in"))
      (node (ref "J7") (pin "6") (pinfunction "S1_6") (pintype "passive"))
      (node (ref "J7") (pin "7") (pinfunction "S2_7") (pintype "power_in"))
      (node (ref "J7") (pin "8") (pinfunction "S3_8") (pintype "power_in"))
      (node (ref "J7") (pin "9") (pinfunction "S4_9") (pintype "power_in"))
      (node (ref "J9") (pin "2") (pinfunction "2_2") (pintype "passive"))
      (node (ref "LED1") (pin "K") (pinfunction "K_K") (pintype "passive"))
      (node (ref "P1") (pin "3") (pinfunction "3_3") (pintype "passive"))
      (node (ref "P2") (pin "2") (pinfunction "2_2") (pintype "passive"))
      (node (ref "P2") (pin "3") (pinfunction "3_3") (pintype "passive"))
      (node (ref "P3") (pin "2") (pinfunction "2_2") (pintype "passive"))
      (node (ref "P4") (pin "1") (pinfunction "1_1") (pintype "passive"))
      (node (ref "P4") (pin "3") (pinfunction "3_3") (pintype "passive"))
      (node (ref "P5") (pin "12") (pinfunction "12_12") (pintype "passive"))
      (node (ref "P5") (pin "2") (pinfunction "2_2") (pintype "passive"))
      (node (ref "P6") (pin "4") (pinfunction "4_4") (pintype "passive"))
      (node (ref "P9") (pin "4") (pinfunction "4_4") (pintype "passive"))
      (node (ref "R13") (pin "1") (pintype "passive"))
      (node (ref "R15") (pin "1") (pintype "passive"))
      (node (ref "R19") (pin "1") (pintype "passive"))
      (node (ref "R2") (pin "1") (pintype "passive"))
      (node (ref "R24") (pin "1") (pintype "passive"))
      (node (ref "R26") (pin "1") (pintype "passive"))
      (node (ref "R27") (pin "1") (pintype "passive"))
      (node (ref "R28") (pin "1") (pintype "passive"))
      (node (ref "R6") (pin "1") (pintype "passive"))
      (node (ref "R7") (pin "1") (pintype "passive"))
      (node (ref "R9") (pin "1") (pintype "passive"))
      (node (ref "T1") (pin "1") (pinfunction "1_1") (pintype "passive"))
      (node (ref "T2") (pin "1") (pinfunction "1_1") (pintype "passive"))
      (node (ref "T3") (pin "1") (pinfunction "1_1") (pintype "passive"))
      (node (ref "T4") (pin "1") (pinfunction "1_1") (pintype "passive"))
      (node (ref "T5") (pin "3") (pinfunction "3_3") (pintype "passive"))
      (node (ref "T6") (pin "3") (pinfunction "3_3") (pintype "passive"))
      (node (ref "U1") (pin "4") (pinfunction "V-_4") (pintype "power_in"))
      (node (ref "U10") (pin "3") (pinfunction "GND_3") (pintype "passive"))
      (node (ref "U2") (pin "4") (pinfunction "V-_4") (pintype "power_in"))
      (node (ref "U3") (pin "4") (pinfunction "V-_4") (pintype "power_in"))
      (node (ref "U4") (pin "4") (pinfunction "V-_4") (pintype "power_in"))
      (node (ref "U5") (pin "4") (pinfunction "COM_4") (pintype "power_in"))
      (node (ref "U6") (pin "3") (pinfunction "GND_3") (pintype "passive"))
      (node (ref "U7") (pin "19") (pinfunction "VSS_19") (pintype "power_in"))
      (node (ref "U7") (pin "8") (pinfunction "VSS_8") (pintype "power_in"))
      (node (ref "U9") (pin "3") (pinfunction "GND_3") (pintype "passive"))
    )
    (net (code "25") (name "Net-(C3-Pad1)") (class "Default")
      (node (ref "C3") (pin "1") (pintype "passive"))
      (node (ref "R1") (pin "2") (pintype "passive"))
    )
    (net (code "26") (name "Net-(C3-Pad2)") (class "Default")
      (node (ref "C3") (pin "2") (pintype "passive"))
      (node (ref "T1") (pin "3") (pinfunction "3_3") (pintype "passive"))
    )
    (net (code "27") (name "Net-(C4-Pad2)") (class "Default")
      (node (ref "C4") (pin "2") (pintype "passive"))
      (node (ref "J2") (pin "2") (pinfunction "2_2") (pintype "passive"))
      (node (ref "R2") (pin "2") (pintype "passive"))
      (node (ref "T1") (pin "6") (pinfunction "6_6") (pintype "passive"))
    )
    (net (code "28") (name "Net-(C6-Pad1)") (class "Default")
      (node (ref "C6") (pin "1") (pintype "passive"))
      (node (ref "R5") (pin "2") (pintype "passive"))
    )
    (net (code "29") (name "Net-(C6-Pad2)") (class "Default")
      (node (ref "C6") (pin "2") (pintype "passive"))
      (node (ref "T2") (pin "3") (pinfunction "3_3") (pintype "passive"))
    )
    (net (code "30") (name "Net-(C7-Pad1)") (class "Default")
      (node (ref "C7") (pin "1") (pintype "passive"))
      (node (ref "R4") (pin "1") (pintype "passive"))
    )
    (net (code "31") (name "Net-(C8-Pad2)") (class "Default")
      (node (ref "C8") (pin "2") (pintype "passive"))
      (node (ref "J3") (pin "2") (pinfunction "2_2") (pintype "passive"))
      (node (ref "R6") (pin "2") (pintype "passive"))
      (node (ref "T2") (pin "6") (pinfunction "6_6") (pintype "passive"))
    )
    (net (code "32") (name "Net-(C9-Pad2)") (class "Default")
      (node (ref "C9") (pin "2") (pintype "passive"))
      (node (ref "R20") (pin "2") (pintype "passive"))
      (node (ref "R28") (pin "2") (pintype "passive"))
      (node (ref "R33") (pin "1") (pintype "passive"))
    )
    (net (code "33") (name "Net-(C11-Pad1)") (class "Default")
      (node (ref "C11") (pin "1") (pintype "passive"))
      (node (ref "R8") (pin "2") (pintype "passive"))
    )
    (net (code "34") (name "Net-(C11-Pad2)") (class "Default")
      (node (ref "C11") (pin "2") (pintype "passive"))
      (node (ref "T3") (pin "3") (pinfunction "3_3") (pintype "passive"))
    )
    (net (code "35") (name "Net-(C13-Pad2)") (class "Default")
      (node (ref "C13") (pin "2") (pintype "passive"))
      (node (ref "J4") (pin "2") (pinfunction "2_2") (pintype "passive"))
      (node (ref "R9") (pin "2") (pintype "passive"))
      (node (ref "T3") (pin "6") (pinfunction "6_6") (pintype "passive"))
    )
    (net (code "36") (name "Net-(C14-Pad1)") (class "Default")
      (node (ref "C14") (pin "1") (pintype "passive"))
      (node (ref "R11") (pin "2") (pintype "passive"))
    )
    (net (code "37") (name "Net-(C14-Pad2)") (class "Default")
      (node (ref "C14") (pin "2") (pintype "passive"))
      (node (ref "T4") (pin "3") (pinfunction "3_3") (pintype "passive"))
    )
    (net (code "38") (name "Net-(C16-Pad1)") (class "Default")
      (node (ref "C16") (pin "1") (pintype "passive"))
      (node (ref "R12") (pin "1") (pintype "passive"))
    )
    (net (code "39") (name "Net-(C17-Pad2)") (class "Default")
      (node (ref "C17") (pin "2") (pintype "passive"))
      (node (ref "J6") (pin "2") (pinfunction "2_2") (pintype "passive"))
      (node (ref "R13") (pin "2") (pintype "passive"))
      (node (ref "T4") (pin "6") (pinfunction "6_6") (pintype "passive"))
    )
    (net (code "40") (name "Net-(C19-Pad1)") (class "Default")
      (node (ref "C19") (pin "1") (pintype "passive"))
      (node (ref "R14") (pin "2") (pintype "passive"))
    )
    (net (code "41") (name "Net-(C19-Pad2)") (class "Default")
      (node (ref "C19") (pin "2") (pintype "passive"))
      (node (ref "T5") (pin "1") (pinfunction "1_1") (pintype "passive"))
    )
    (net (code "42") (name "Net-(C21-Pad2)") (class "Default")
      (node (ref "C21") (pin "2") (pintype "passive"))
      (node (ref "K1") (pin "2") (pinfunction "2_2") (pintype "passive"))
      (node (ref "K1") (pin "3") (pinfunction "3_3") (pintype "passive"))
      (node (ref "K1") (pin "4") (pinfunction "4_4") (pintype "passive"))
      (node (ref "K1") (pin "5") (pinfunction "5_5") (pintype "passive"))
      (node (ref "R15") (pin "2") (pintype "passive"))
      (node (ref "T5") (pin "4") (pinfunction "4_4") (pintype "passive"))
    )
    (net (code "43") (name "Net-(C22-Pad1)") (class "Default")
      (node (ref "C22") (pin "1") (pintype "passive"))
      (node (ref "R17") (pin "2") (pintype "passive"))
    )
    (net (code "44") (name "Net-(C22-Pad2)") (class "Default")
      (node (ref "C22") (pin "2") (pintype "passive"))
      (node (ref "T6") (pin "1") (pinfunction "1_1") (pintype "passive"))
    )
    (net (code "45") (name "Net-(C24-Pad1)") (class "Default")
      (node (ref "C24") (pin "1") (pintype "passive"))
      (node (ref "R18") (pin "1") (pintype "passive"))
    )
    (net (code "46") (name "Net-(C25-Pad2)") (class "Default")
      (node (ref "C25") (pin "2") (pintype "passive"))
      (node (ref "K2") (pin "2") (pinfunction "2_2") (pintype "passive"))
      (node (ref "K2") (pin "3") (pinfunction "3_3") (pintype "passive"))
      (node (ref "K2") (pin "4") (pinfunction "4_4") (pintype "passive"))
      (node (ref "K2") (pin "5") (pinfunction "5_5") (pintype "passive"))
      (node (ref "R19") (pin "2") (pintype "passive"))
      (node (ref "T6") (pin "4") (pinfunction "4_4") (pintype "passive"))
    )
    (net (code "47") (name "Net-(C26-Pad1)") (class "Default")
      (node (ref "C26") (pin "1") (pintype "passive"))
      (node (ref "C45") (pin "2") (pintype "passive"))
      (node (ref "L1") (pin "2") (pintype "passive"))
    )
    (net (code "48") (name "Net-(C26-Pad2)") (class "Default")
      (node (ref "C26") (pin "2") (pintype "passive"))
      (node (ref "R22") (pin "1") (pintype "passive"))
    )
    (net (code "49") (name "Net-(C31-Pad2)") (class "Default")
      (node (ref "C31") (pin "2") (pintype "passive"))
      (node (ref "L2") (pin "2") (pintype "passive"))
      (node (ref "L3") (pin "1") (pintype "passive"))
    )
    (net (code "50") (name "Net-(C41-Pad2)") (class "Default")
      (node (ref "C41") (pin "2") (pintype "passive"))
      (node (ref "J8") (pin "2") (pinfunction "2_2") (pintype "passive"))
      (node (ref "L4") (pin "1") (pintype "passive"))
      (node (ref "R7") (pin "2") (pintype "passive"))
    )
    (net (code "51") (name "Net-(C44-Pad2)") (class "Default")
      (node (ref "C44") (pin "2") (pintype "passive"))
      (node (ref "L1") (pin "1") (pintype "passive"))
      (node (ref "L3") (pin "2") (pintype "passive"))
    )
    (net (code "52") (name "Net-(C46-Pad2)") (class "Default")
      (node (ref "C46") (pin "2") (pintype "passive"))
      (node (ref "L4") (pin "2") (pintype "passive"))
      (node (ref "L5") (pin "1") (pintype "passive"))
    )
    (net (code "53") (name "Net-(F1-Pad2)") (class "Default")
      (node (ref "F1") (pin "2") (pintype "passive"))
      (node (ref "P3") (pin "1") (pinfunction "1_1") (pintype "passive"))
    )
    (net (code "54") (name "Net-(J1-Signal)") (class "Default")
      (node (ref "J1") (pin "1") (pinfunction "Signal_1") (pintype "input"))
      (node (ref "J10") (pin "2") (pinfunction "2_2") (pintype "passive"))
      (node (ref "U9") (pin "2") (pinfunction "2_2") (pintype "input"))
    )
    (net (code "55") (name "Net-(J2-Pad1)") (class "Default")
      (node (ref "J2") (pin "1") (pinfunction "1_1") (pintype "input"))
      (node (ref "T1") (pin "4") (pinfunction "4_4") (pintype "passive"))
    )
    (net (code "56") (name "Net-(J3-Pad1)") (class "Default")
      (node (ref "J3") (pin "1") (pinfunction "1_1") (pintype "input"))
      (node (ref "T2") (pin "4") (pinfunction "4_4") (pintype "passive"))
    )
    (net (code "57") (name "Net-(J4-Pad1)") (class "Default")
      (node (ref "J4") (pin "1") (pinfunction "1_1") (pintype "input"))
      (node (ref "T3") (pin "4") (pinfunction "4_4") (pintype "passive"))
    )
    (net (code "58") (name "Net-(J6-Pad1)") (class "Default")
      (node (ref "J6") (pin "1") (pinfunction "1_1") (pintype "input"))
      (node (ref "T4") (pin "4") (pinfunction "4_4") (pintype "passive"))
    )
    (net (code "59") (name "Net-(K1-Pad1)") (class "Default")
      (node (ref "K1") (pin "1") (pinfunction "1_1") (pintype "passive"))
      (node (ref "T5") (pin "6") (pinfunction "6_6") (pintype "passive"))
    )
    (net (code "60") (name "Net-(K2-Pad1)") (class "Default")
      (node (ref "K2") (pin "1") (pinfunction "1_1") (pintype "passive"))
      (node (ref "T6") (pin "6") (pinfunction "6_6") (pintype "passive"))
    )
    (net (code "61") (name "Net-(LED1-PadA)") (class "Default")
      (node (ref "LED1") (pin "A") (pinfunction "A_A") (pintype "passive"))
      (node (ref "R21") (pin "1") (pintype "passive"))
    )
    (net (code "62") (name "Net-(U1-IN-)") (class "Default")
      (node (ref "C5") (pin "1") (pintype "passive"))
      (node (ref "R3") (pin "1") (pintype "passive"))
      (node (ref "R4") (pin "2") (pintype "passive"))
      (node (ref "U1") (pin "2") (pinfunction "IN-_2") (pintype "input"))
    )
    (net (code "63") (name "Net-(U1-OUT)") (class "Default")
      (node (ref "C5") (pin "2") (pintype "passive"))
      (node (ref "R1") (pin "1") (pintype "passive"))
      (node (ref "R3") (pin "2") (pintype "passive"))
      (node (ref "R5") (pin "1") (pintype "passive"))
      (node (ref "U1") (pin "6") (pinfunction "OUT_6") (pintype "output"))
    )
    (net (code "64") (name "Net-(U2-IN+)") (class "Default")
      (node (ref "R20") (pin "1") (pintype "passive"))
      (node (ref "U2") (pin "3") (pinfunction "IN+_3") (pintype "input"))
    )
    (net (code "65") (name "Net-(U2-IN-)") (class "Default")
      (node (ref "C27") (pin "1") (pintype "passive"))
      (node (ref "R22") (pin "2") (pintype "passive"))
      (node (ref "R23") (pin "1") (pintype "passive"))
      (node (ref "U2") (pin "2") (pinfunction "IN-_2") (pintype "input"))
    )
    (net (code "66") (name "Net-(U2-OUT)") (class "Default")
      (node (ref "C27") (pin "2") (pintype "passive"))
      (node (ref "J8") (pin "1") (pinfunction "1_1") (pintype "passive"))
      (node (ref "R23") (pin "2") (pintype "passive"))
      (node (ref "U2") (pin "6") (pinfunction "OUT_6") (pintype "output"))
    )
    (net (code "67") (name "Net-(U3-OUT)") (class "Default")
      (node (ref "C15") (pin "2") (pintype "passive"))
      (node (ref "R10") (pin "2") (pintype "passive"))
      (node (ref "R11") (pin "1") (pintype "passive"))
      (node (ref "R8") (pin "1") (pintype "passive"))
      (node (ref "U3") (pin "6") (pinfunction "OUT_6") (pintype "output"))
    )
    (net (code "68") (name "Net-(U4-IN-)") (class "Default")
      (node (ref "C23") (pin "1") (pintype "passive"))
      (node (ref "R16") (pin "1") (pintype "passive"))
      (node (ref "R18") (pin "2") (pintype "passive"))
      (node (ref "U4") (pin "2") (pinfunction "IN-_2") (pintype "input"))
    )
    (net (code "69") (name "Net-(U4-OUT)") (class "Default")
      (node (ref "C23") (pin "2") (pintype "passive"))
      (node (ref "R14") (pin "1") (pintype "passive"))
      (node (ref "R16") (pin "2") (pintype "passive"))
      (node (ref "R17") (pin "1") (pintype "passive"))
      (node (ref "U4") (pin "6") (pinfunction "OUT_6") (pintype "output"))
    )
    (net (code "70") (name "Net-(U7-VUSB3V3)") (class "Default")
      (node (ref "C36") (pin "1") (pintype "passive"))
      (node (ref "U7") (pin "14") (pinfunction "VUSB3V3_14") (pintype "power_in"))
    )
    (net (code "71") (name "Net-(U10-3)") (class "Default")
      (node (ref "U10") (pin "4") (pinfunction "3_4") (pintype "output"))
      (node (ref "U7") (pin "18") (pinfunction "RC7_18") (pintype "bidirectional"))
    )
    (net (code "72") (name "VGPSDO") (class "Default")
      (node (ref "C39") (pin "1") (pintype "passive"))
      (node (ref "FB1") (pin "2") (pintype "passive"))
      (node (ref "P2") (pin "1") (pinfunction "1_1") (pintype "passive"))
    )
    (net (code "73") (name "VUSB") (class "Default")
      (node (ref "J7") (pin "1") (pinfunction "VBus_1") (pintype "power_in"))
      (node (ref "P9") (pin "1") (pinfunction "1_1") (pintype "passive"))
      (node (ref "R25") (pin "2") (pintype "passive"))
    )
    (net (code "74") (name "Vamp") (class "Default")
      (node (ref "C1") (pin "1") (pintype "passive"))
      (node (ref "C10") (pin "1") (pintype "passive"))
      (node (ref "C12") (pin "1") (pintype "passive"))
      (node (ref "C18") (pin "1") (pintype "passive"))
      (node (ref "C2") (pin "1") (pintype "passive"))
      (node (ref "C20") (pin "1") (pintype "passive"))
      (node (ref "C34") (pin "1") (pintype "passive"))
      (node (ref "C35") (pin "1") (pintype "passive"))
      (node (ref "C40") (pin "1") (pintype "passive"))
      (node (ref "C42") (pin "1") (pintype "passive"))
      (node (ref "C43") (pin "1") (pintype "passive"))
      (node (ref "R33") (pin "2") (pintype "passive"))
      (node (ref "U1") (pin "7") (pinfunction "V+_7") (pintype "power_in"))
      (node (ref "U2") (pin "7") (pinfunction "V+_7") (pintype "power_in"))
      (node (ref "U3") (pin "7") (pinfunction "V+_7") (pintype "power_in"))
      (node (ref "U4") (pin "7") (pinfunction "V+_7") (pintype "power_in"))
      (node (ref "U5") (pin "3") (pinfunction "OUT_3") (pintype "power_in"))
    )
    (net (code "75") (name "unconnected-(J7-ID-Pad4)") (class "Default")
      (node (ref "J7") (pin "4") (pinfunction "ID_4") (pintype "passive"))
    )
    (net (code "76") (name "unconnected-(T1-Pad2)") (class "Default")
      (node (ref "T1") (pin "2") (pinfunction "2_2") (pintype "passive"))
    )
    (net (code "77") (name "unconnected-(T1-Pad5)") (class "Default")
      (node (ref "T1") (pin "5") (pinfunction "5_5") (pintype "passive"))
    )
    (net (code "78") (name "unconnected-(T2-Pad2)") (class "Default")
      (node (ref "T2") (pin "2") (pinfunction "2_2") (pintype "passive"))
    )
    (net (code "79") (name "unconnected-(T2-Pad5)") (class "Default")
      (node (ref "T2") (pin "5") (pinfunction "5_5") (pintype "passive"))
    )
    (net (code "80") (name "unconnected-(T3-Pad2)") (class "Default")
      (node (ref "T3") (pin "2") (pinfunction "2_2") (pintype "passive"))
    )
    (net (code "81") (name "unconnected-(T3-Pad5)") (class "Default")
      (node (ref "T3") (pin "5") (pinfunction "5_5") (pintype "passive"))
    )
    (net (code "82") (name "unconnected-(T4-Pad2)") (class "Default")
      (node (ref "T4") (pin "2") (pinfunction "2_2") (pintype "passive"))
    )
    (net (code "83") (name "unconnected-(T4-Pad5)") (class "Default")
      (node (ref "T4") (pin "5") (pinfunction "5_5") (pintype "passive"))
    )
    (net (code "84") (name "unconnected-(T5-Pad2)") (class "Default")
      (node (ref "T5") (pin "2") (pinfunction "2_2") (pintype "passive"))
    )
    (net (code "85") (name "unconnected-(T5-Pad5)") (class "Default")
      (node (ref "T5") (pin "5") (pinfunction "5_5") (pintype "passive"))
    )
    (net (code "86") (name "unconnected-(T6-Pad2)") (class "Default")
      (node (ref "T6") (pin "2") (pinfunction "2_2") (pintype "passive"))
    )
    (net (code "87") (name "unconnected-(T6-Pad5)") (class "Default")
      (node (ref "T6") (pin "5") (pinfunction "5_5") (pintype "passive"))
    )
    (net (code "88") (name "unconnected-(U1-NC-Pad1)") (class "Default")
      (node (ref "U1") (pin "1") (pinfunction "NC_1") (pintype "passive"))
    )
    (net (code "89") (name "unconnected-(U1-NC-Pad5)") (class "Default")
      (node (ref "U1") (pin "5") (pinfunction "NC_5") (pintype "passive"))
    )
    (net (code "90") (name "unconnected-(U1-NC-Pad8)") (class "Default")
      (node (ref "U1") (pin "8") (pinfunction "NC_8") (pintype "passive"))
    )
    (net (code "91") (name "unconnected-(U2-NC-Pad1)") (class "Default")
      (node (ref "U2") (pin "1") (pinfunction "NC_1") (pintype "passive"))
    )
    (net (code "92") (name "unconnected-(U2-NC-Pad5)") (class "Default")
      (node (ref "U2") (pin "5") (pinfunction "NC_5") (pintype "passive"))
    )
    (net (code "93") (name "unconnected-(U2-NC-Pad8)") (class "Default")
      (node (ref "U2") (pin "8") (pinfunction "NC_8") (pintype "passive"))
    )
    (net (code "94") (name "unconnected-(U3-NC-Pad1)") (class "Default")
      (node (ref "U3") (pin "1") (pinfunction "NC_1") (pintype "passive"))
    )
    (net (code "95") (name "unconnected-(U3-NC-Pad5)") (class "Default")
      (node (ref "U3") (pin "5") (pinfunction "NC_5") (pintype "passive"))
    )
    (net (code "96") (name "unconnected-(U3-NC-Pad8)") (class "Default")
      (node (ref "U3") (pin "8") (pinfunction "NC_8") (pintype "passive"))
    )
    (net (code "97") (name "unconnected-(U4-NC-Pad1)") (class "Default")
      (node (ref "U4") (pin "1") (pinfunction "NC_1") (pintype "passive"))
    )
    (net (code "98") (name "unconnected-(U4-NC-Pad5)") (class "Default")
      (node (ref "U4") (pin "5") (pinfunction "NC_5") (pintype "passive"))
    )
    (net (code "99") (name "unconnected-(U4-NC-Pad8)") (class "Default")
      (node (ref "U4") (pin "8") (pinfunction "NC_8") (pintype "passive"))
    )
    (net (code "100") (name "unconnected-(U7-RA2-Pad4)") (class "Default")
      (node (ref "U7") (pin "4") (pinfunction "RA2_4") (pintype "bidirectional"))
    )
    (net (code "101") (name "unconnected-(U7-RA4-Pad6)") (class "Default")
      (node (ref "U7") (pin "6") (pinfunction "RA4_6") (pintype "bidirectional"))
    )
    (net (code "102") (name "unconnected-(U7-RA6-Pad10)") (class "Default")
      (node (ref "U7") (pin "10") (pinfunction "RA6_10") (pintype "bidirectional"))
    )
    (net (code "103") (name "unconnected-(U7-RA7-Pad9)") (class "Default")
      (node (ref "U7") (pin "9") (pinfunction "RA7_9") (pintype "bidirectional"))
    )
    (net (code "104") (name "unconnected-(U7-RC0-Pad11)") (class "Default")
      (node (ref "U7") (pin "11") (pinfunction "RC0_11") (pintype "bidirectional"))
    )
    (net (code "105") (name "unconnected-(U7-RC2-Pad13)") (class "Default")
      (node (ref "U7") (pin "13") (pinfunction "RC2_13") (pintype "bidirectional"))
    )
  )
)
